# E16-PDB-7-LOAD_3.net
KiCad netlist of a schematic drawn in Altium Designer
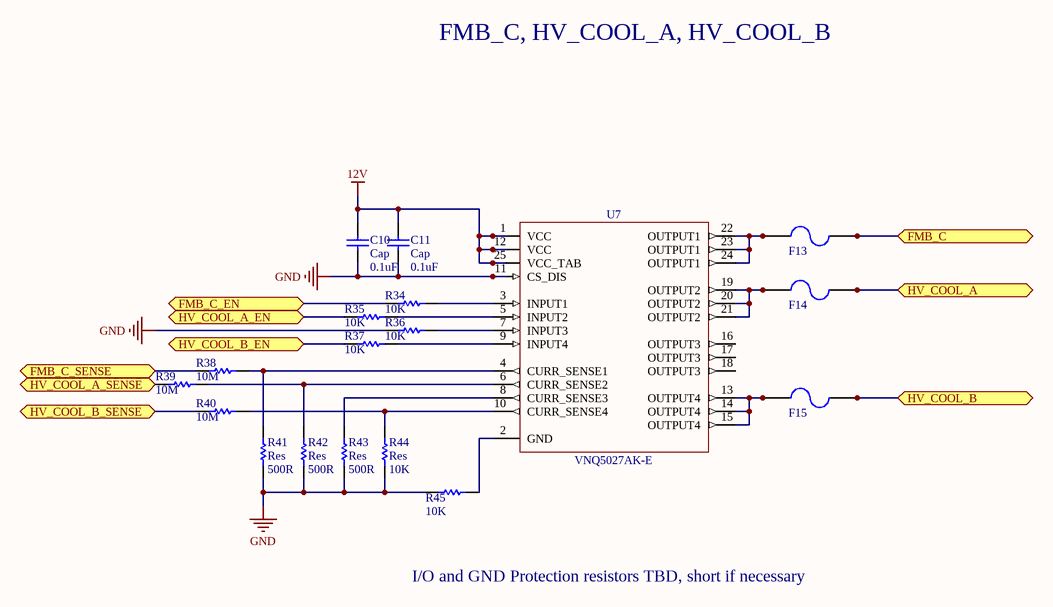
[diagram p0: E16-PDB-7-LOAD_3.SchDoc]

(export (version "E")
  (design (tool "Eeschema 10.0.6"))
  (components
    (comp (ref "C10")
      (value "Cap")
      (footprint "C0805")
      (description "Capacitor")
      (fields (field (name "ALTIUM_VALUE") "0.1uF") (field (name "PUBLISHER") "Altium Limited"))
      (libsource (lib "Capacitors") (part "Cap"))
    )
    (comp (ref "C11")
      (value "Cap")
      (footprint "C0805")
      (description "Capacitor")
      (fields (field (name "ALTIUM_VALUE") "0.1uF") (field (name "PUBLISHER") "Altium Limited"))
      (libsource (lib "Capacitors") (part "Cap"))
    )
    (comp (ref "F13")
      (value "BK-6013")
      (footprint "BK-6013")
      (description "FUSE HOLDER BLADE PCB")
      (libsource (lib "Fuses") (part "BK-6013"))
    )
    (comp (ref "F14")
      (value "BK-6013")
      (footprint "BK-6013")
      (description "FUSE HOLDER BLADE PCB")
      (libsource (lib "Fuses") (part "BK-6013"))
    )
    (comp (ref "F15")
      (value "BK-6013")
      (footprint "BK-6013")
      (description "FUSE HOLDER BLADE PCB")
      (libsource (lib "Fuses") (part "BK-6013"))
    )
    (comp (ref "R34")
      (value "10K")
      (footprint "2012[0805]")
      (description "Surface Mount Resistor")
      (fields (field (name "Comment") "Res") (field (name "PUBLISHER") "Altium Limited"))
      (libsource (lib "Resistors") (part "Res"))
    )
    (comp (ref "R35")
      (value "10K")
      (footprint "2012[0805]")
      (description "Surface Mount Resistor")
      (fields (field (name "Comment") "Res") (field (name "PUBLISHER") "Altium Limited"))
      (libsource (lib "Resistors") (part "Res"))
    )
    (comp (ref "R36")
      (value "10K")
      (footprint "2012[0805]")
      (description "Surface Mount Resistor")
      (fields (field (name "Comment") "Res") (field (name "PUBLISHER") "Altium Limited"))
      (libsource (lib "Resistors") (part "Res"))
    )
    (comp (ref "R37")
      (value "10K")
      (footprint "2012[0805]")
      (description "Surface Mount Resistor")
      (fields (field (name "Comment") "Res") (field (name "PUBLISHER") "Altium Limited"))
      (libsource (lib "Resistors") (part "Res"))
    )
    (comp (ref "R38")
      (value "10M")
      (footprint "2012[0805]")
      (description "Surface Mount Resistor")
      (fields (field (name "Comment") "Res") (field (name "PUBLISHER") "Altium Limited"))
      (libsource (lib "Resistors") (part "Res"))
    )
    (comp (ref "R39")
      (value "10M")
      (footprint "2012[0805]")
      (description "Surface Mount Resistor")
      (fields (field (name "Comment") "Res") (field (name "PUBLISHER") "Altium Limited"))
      (libsource (lib "Resistors") (part "Res"))
    )
    (comp (ref "R40")
      (value "10M")
      (footprint "2012[0805]")
      (description "Surface Mount Resistor")
      (fields (field (name "Comment") "Res") (field (name "PUBLISHER") "Altium Limited"))
      (libsource (lib "Resistors") (part "Res"))
    )
    (comp (ref "R41")
      (value "Res")
      (footprint "2012[0805]")
      (description "Surface Mount Resistor")
      (fields (field (name "ALTIUM_VALUE") "500R") (field (name "PUBLISHER") "Altium Limited"))
      (libsource (lib "Resistors") (part "Res"))
    )
    (comp (ref "R42")
      (value "Res")
      (footprint "2012[0805]")
      (description "Surface Mount Resistor")
      (fields (field (name "ALTIUM_VALUE") "500R") (field (name "PUBLISHER") "Altium Limited"))
      (libsource (lib "Resistors") (part "Res"))
    )
    (comp (ref "R43")
      (value "Res")
      (footprint "2012[0805]")
      (description "Surface Mount Resistor")
      (fields (field (name "ALTIUM_VALUE") "500R") (field (name "PUBLISHER") "Altium Limited"))
      (libsource (lib "Resistors") (part "Res"))
    )
    (comp (ref "R44")
      (value "Res")
      (footprint "2012[0805]")
      (description "Surface Mount Resistor")
      (fields (field (name "ALTIUM_VALUE") "10K") (field (name "PUBLISHER") "Altium Limited"))
      (libsource (lib "Resistors") (part "Res"))
    )
    (comp (ref "R45")
      (value "10K")
      (footprint "2012[0805]")
      (description "Surface Mount Resistor")
      (fields (field (name "Comment") "Res") (field (name "PUBLISHER") "Altium Limited"))
      (libsource (lib "Resistors") (part "Res"))
    )
    (comp (ref "U7")
      (value "U_VNQ5027AK-E")
      (footprint "PowerSSO-24")
      (description "LOAD CHANNEL HIGH SIDE 42 A 4 Channel")
      (fields (field (name "MFG") "STmicroelectronics") (field (name "MFG_PN") "VNQ5027AK-E"))
      (libsource (lib "Transistors") (part "U_VNQ5027AK-E"))
    )
  )
  (nets
    (net (code "1") (name "/FMB_C") (class "Default")
      (node (ref "F13") (pin "3") (pinfunction "3_3") (pintype "passive"))
      (node (ref "F13") (pin "4") (pinfunction "4_4") (pintype "passive"))
    )
    (net (code "2") (name "/FMB_C_EN") (class "Default")
      (node (ref "R34") (pin "2") (pinfunction "2_2") (pintype "passive"))
    )
    (net (code "3") (name "/FMB_C_SENSE") (class "Default")
      (node (ref "R38") (pin "2") (pinfunction "2_2") (pintype "passive"))
    )
    (net (code "4") (name "/HV_COOL_A") (class "Default")
      (node (ref "F14") (pin "3") (pinfunction "3_3") (pintype "passive"))
      (node (ref "F14") (pin "4") (pinfunction "4_4") (pintype "passive"))
    )
    (net (code "5") (name "/HV_COOL_A_EN") (class "Default")
      (node (ref "R35") (pin "2") (pinfunction "2_2") (pintype "passive"))
    )
    (net (code "6") (name "/HV_COOL_A_SENSE") (class "Default")
      (node (ref "R39") (pin "2") (pinfunction "2_2") (pintype "passive"))
    )
    (net (code "7") (name "/HV_COOL_B") (class "Default")
      (node (ref "F15") (pin "3") (pinfunction "3_3") (pintype "passive"))
      (node (ref "F15") (pin "4") (pinfunction "4_4") (pintype "passive"))
    )
    (net (code "8") (name "/HV_COOL_B_EN") (class "Default")
      (node (ref "R37") (pin "2") (pinfunction "2_2") (pintype "passive"))
    )
    (net (code "9") (name "/HV_COOL_B_SENSE") (class "Default")
      (node (ref "R40") (pin "2") (pinfunction "2_2") (pintype "passive"))
    )
    (net (code "10") (name "12V") (class "Default")
      (node (ref "C10") (pin "2") (pinfunction "2_2") (pintype "passive"))
      (node (ref "C11") (pin "2") (pinfunction "2_2") (pintype "passive"))
      (node (ref "U7") (pin "1") (pinfunction "VCC_1") (pintype "power_in"))
      (node (ref "U7") (pin "12") (pinfunction "VCC_12") (pintype "power_in"))
      (node (ref "U7") (pin "25") (pinfunction "VCC_TAB_25") (pintype "power_in"))
    )
    (net (code "11") (name "GND") (class "Default")
      (node (ref "C10") (pin "1") (pinfunction "1_1") (pintype "passive"))
      (node (ref "C11") (pin "1") (pinfunction "1_1") (pintype "passive"))
      (node (ref "R36") (pin "2") (pinfunction "2_2") (pintype "passive"))
      (node (ref "R41") (pin "1") (pinfunction "1_1") (pintype "passive"))
      (node (ref "R42") (pin "1") (pinfunction "1_1") (pintype "passive"))
      (node (ref "R43") (pin "1") (pinfunction "1_1") (pintype "passive"))
      (node (ref "R44") (pin "1") (pinfunction "1_1") (pintype "passive"))
      (node (ref "R45") (pin "2") (pinfunction "2_2") (pintype "passive"))
      (node (ref "U7") (pin "11") (pinfunction "CS_DIS_11") (pintype "input"))
    )
    (net (code "12") (name "Net-(F13-Pad1)") (class "Default")
      (node (ref "F13") (pin "1") (pinfunction "1_1") (pintype "passive"))
      (node (ref "F13") (pin "2") (pinfunction "2_2") (pintype "passive"))
      (node (ref "U7") (pin "22") (pinfunction "OUTPUT1_22") (pintype "output"))
      (node (ref "U7") (pin "23") (pinfunction "OUTPUT1_23") (pintype "output"))
      (node (ref "U7") (pin "24") (pinfunction "OUTPUT1_24") (pintype "output"))
    )
    (net (code "13") (name "Net-(F14-Pad1)") (class "Default")
      (node (ref "F14") (pin "1") (pinfunction "1_1") (pintype "passive"))
      (node (ref "F14") (pin "2") (pinfunction "2_2") (pintype "passive"))
      (node (ref "U7") (pin "19") (pinfunction "OUTPUT2_19") (pintype "output"))
      (node (ref "U7") (pin "20") (pinfunction "OUTPUT2_20") (pintype "output"))
      (node (ref "U7") (pin "21") (pinfunction "OUTPUT2_21") (pintype "output"))
    )
    (net (code "14") (name "Net-(F15-Pad1)") (class "Default")
      (node (ref "F15") (pin "1") (pinfunction "1_1") (pintype "passive"))
      (node (ref "F15") (pin "2") (pinfunction "2_2") (pintype "passive"))
      (node (ref "U7") (pin "13") (pinfunction "OUTPUT4_13") (pintype "output"))
      (node (ref "U7") (pin "14") (pinfunction "OUTPUT4_14") (pintype "output"))
      (node (ref "U7") (pin "15") (pinfunction "OUTPUT4_15") (pintype "output"))
    )
    (net (code "15") (name "Net-(U7-CURR_SENSE1)") (class "Default")
      (node (ref "R38") (pin "1") (pinfunction "1_1") (pintype "passive"))
      (node (ref "R41") (pin "2") (pinfunction "2_2") (pintype "passive"))
      (node (ref "U7") (pin "4") (pinfunction "CURR_SENSE1_4") (pintype "output"))
    )
    (net (code "16") (name "Net-(U7-CURR_SENSE2)") (class "Default")
      (node (ref "R39") (pin "1") (pinfunction "1_1") (pintype "passive"))
      (node (ref "R42") (pin "2") (pinfunction "2_2") (pintype "passive"))
      (node (ref "U7") (pin "6") (pinfunction "CURR_SENSE2_6") (pintype "output"))
    )
    (net (code "17") (name "Net-(U7-CURR_SENSE3)") (class "Default")
      (node (ref "R43") (pin "2") (pinfunction "2_2") (pintype "passive"))
      (node (ref "U7") (pin "8") (pinfunction "CURR_SENSE3_8") (pintype "output"))
    )
    (net (code "18") (name "Net-(U7-CURR_SENSE4)") (class "Default")
      (node (ref "R40") (pin "1") (pinfunction "1_1") (pintype "passive"))
      (node (ref "R44") (pin "2") (pinfunction "2_2") (pintype "passive"))
      (node (ref "U7") (pin "10") (pinfunction "CURR_SENSE4_10") (pintype "output"))
    )
    (net (code "19") (name "Net-(U7-GND)") (class "Default")
      (node (ref "R45") (pin "1") (pinfunction "1_1") (pintype "passive"))
      (node (ref "U7") (pin "2") (pinfunction "GND_2") (pintype "power_in"))
    )
    (net (code "20") (name "Net-(U7-INPUT1)") (class "Default")
      (node (ref "R34") (pin "1") (pinfunction "1_1") (pintype "passive"))
      (node (ref "U7") (pin "3") (pinfunction "INPUT1_3") (pintype "input"))
    )
    (net (code "21") (name "Net-(U7-INPUT2)") (class "Default")
      (node (ref "R35") (pin "1") (pinfunction "1_1") (pintype "passive"))
      (node (ref "U7") (pin "5") (pinfunction "INPUT2_5") (pintype "input"))
    )
    (net (code "22") (name "Net-(U7-INPUT3)") (class "Default")
      (node (ref "R36") (pin "1") (pinfunction "1_1") (pintype "passive"))
      (node (ref "U7") (pin "7") (pinfunction "INPUT3_7") (pintype "input"))
    )
    (net (code "23") (name "Net-(U7-INPUT4)") (class "Default")
      (node (ref "R37") (pin "1") (pinfunction "1_1") (pintype "passive"))
      (node (ref "U7") (pin "9") (pinfunction "INPUT4_9") (pintype "input"))
    )
    (net (code "24") (name "unconnected-(U7-OUTPUT3-Pad16)") (class "Default")
      (node (ref "U7") (pin "16") (pinfunction "OUTPUT3_16") (pintype "output"))
    )
    (net (code "25") (name "unconnected-(U7-OUTPUT3-Pad17)") (class "Default")
      (node (ref "U7") (pin "17") (pinfunction "OUTPUT3_17") (pintype "output"))
    )
    (net (code "26") (name "unconnected-(U7-OUTPUT3-Pad18)") (class "Default")
      (node (ref "U7") (pin "18") (pinfunction "OUTPUT3_18") (pintype "output"))
    )
  )
)
